# ProPrj_BS4C_00006_03_EasyEDA_2025-07-22.net
KiCad netlist of a schematic drawn in EasyEDA Pro
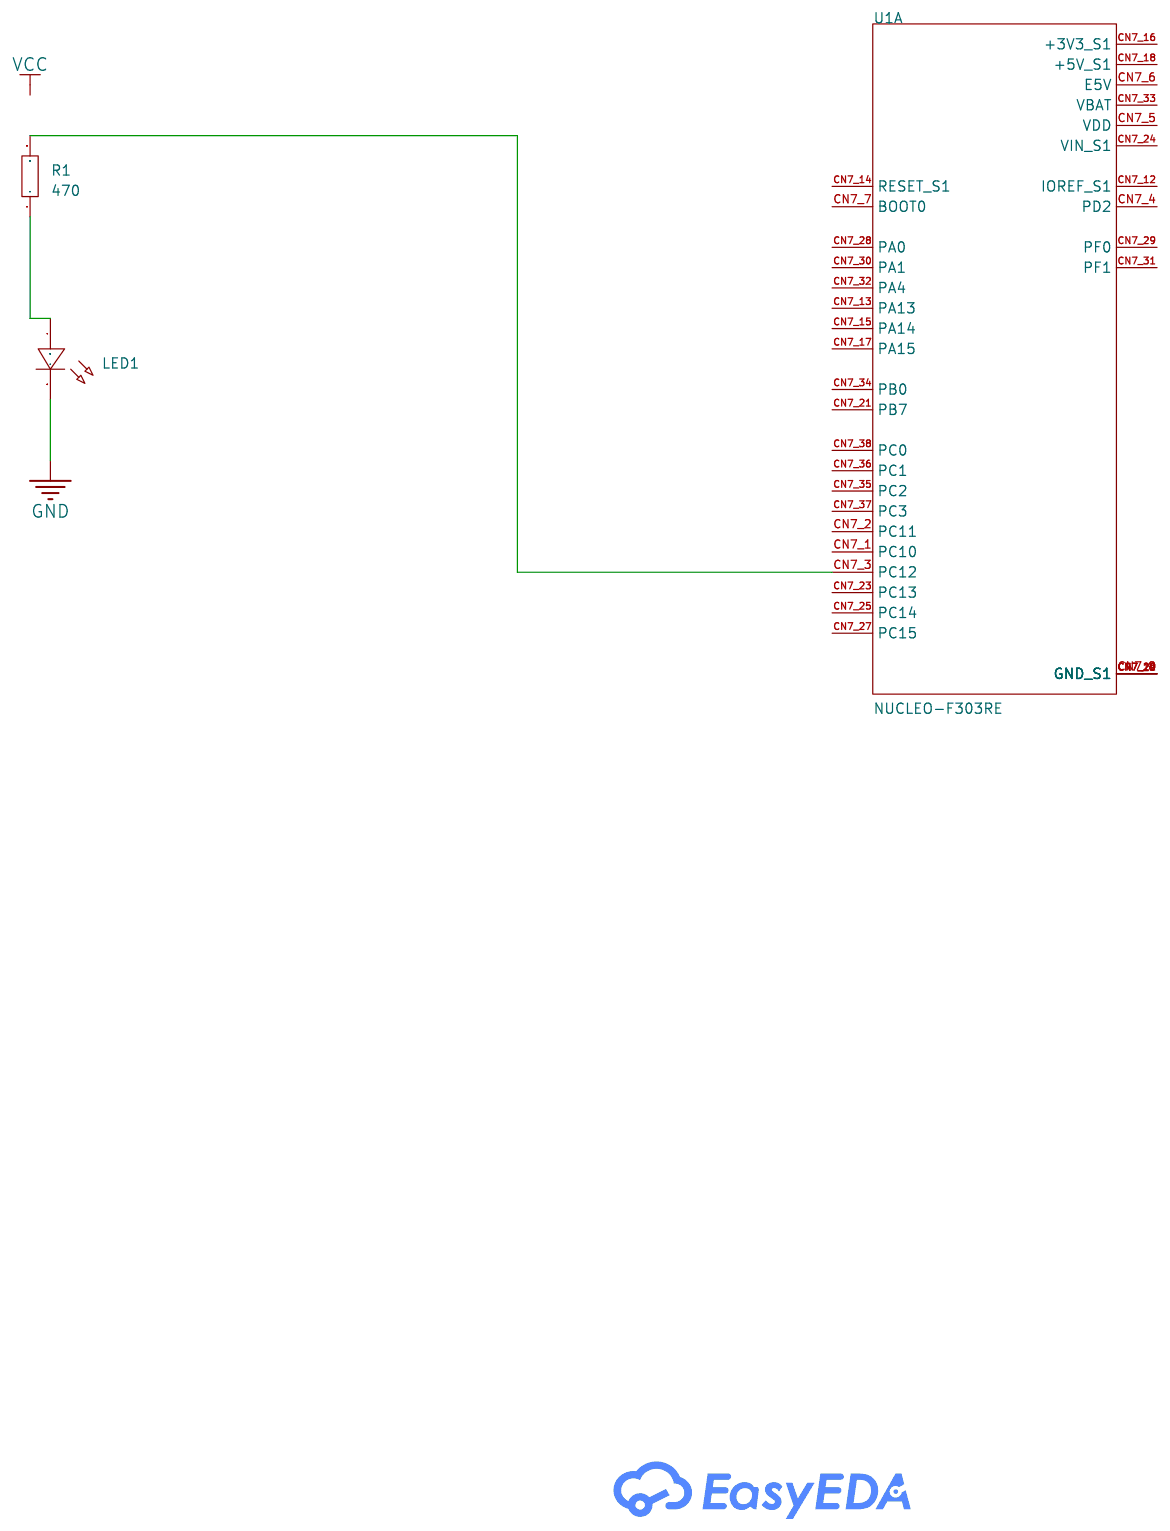
[diagram p0: schematic sheet]

(export (version "E")
  (design (tool "Eeschema 10.0.6"))
  (components
    (comp (ref "LED1")
      (value "~")
      (footprint "easyedapro:LED-TH_BD3.0-P2.54-FD")
      (libsource (lib "easyedapro") (part "LED_TH-R"))
    )
    (comp (ref "R1") (value "470") (footprint "easyedapro:R1210") (libsource (lib "easyedapro") (part "Res")))
    (comp (ref "U1") (value "NUCLEO-F303RE") (libsource (lib "easyedapro") (part "NUCLEO-F303RE")))
  )
  (nets
    (net (code "1") (name "GND") (class "Default")
      (node (ref "LED1") (pin "2") (pinfunction "A_2") (pintype "input"))
    )
    (net (code "2") (name "Net-(LED1-C)") (class "Default")
      (node (ref "LED1") (pin "1") (pinfunction "C_1") (pintype "input"))
      (node (ref "R1") (pin "1") (pinfunction "1_1") (pintype "input"))
    )
    (net (code "3") (name "Net-(U1A-GND_S1-PadCN7_19)") (class "Default")
      (node (ref "U1") (pin "CN7_19") (pinfunction "GND_S1_CN7_19") (pintype "unspecified"))
      (node (ref "U1") (pin "CN7_20") (pinfunction "GND_S1_CN7_20") (pintype "unspecified"))
      (node (ref "U1") (pin "CN7_22") (pinfunction "GND_S1_CN7_22") (pintype "unspecified"))
      (node (ref "U1") (pin "CN7_8") (pinfunction "GND_S1_CN7_8") (pintype "unspecified"))
    )
    (net (code "4") (name "Net-(U1A-PC12)") (class "Default")
      (node (ref "R1") (pin "2") (pinfunction "2_2") (pintype "input"))
      (node (ref "U1") (pin "CN7_3") (pinfunction "PC12_CN7_3") (pintype "bidirectional"))
    )
    (net (code "6") (name "unconnected-(U1A-+3V3_S1-PadCN7_16)") (class "Default")
      (node (ref "U1") (pin "CN7_16") (pinfunction "+3V3_S1_CN7_16") (pintype "unspecified"))
    )
    (net (code "7") (name "unconnected-(U1A-+5V_S1-PadCN7_18)") (class "Default")
      (node (ref "U1") (pin "CN7_18") (pinfunction "+5V_S1_CN7_18") (pintype "unspecified"))
    )
    (net (code "8") (name "unconnected-(U1A-BOOT0-PadCN7_7)") (class "Default")
      (node (ref "U1") (pin "CN7_7") (pinfunction "BOOT0_CN7_7") (pintype "bidirectional"))
    )
    (net (code "9") (name "unconnected-(U1A-E5V-PadCN7_6)") (class "Default")
      (node (ref "U1") (pin "CN7_6") (pinfunction "E5V_CN7_6") (pintype "unspecified"))
    )
    (net (code "10") (name "unconnected-(U1A-IOREF_S1-PadCN7_12)") (class "Default")
      (node (ref "U1") (pin "CN7_12") (pinfunction "IOREF_S1_CN7_12") (pintype "bidirectional"))
    )
    (net (code "11") (name "unconnected-(U1A-PA0-PadCN7_28)") (class "Default")
      (node (ref "U1") (pin "CN7_28") (pinfunction "PA0_CN7_28") (pintype "bidirectional"))
    )
    (net (code "12") (name "unconnected-(U1A-PA1-PadCN7_30)") (class "Default")
      (node (ref "U1") (pin "CN7_30") (pinfunction "PA1_CN7_30") (pintype "bidirectional"))
    )
    (net (code "13") (name "unconnected-(U1A-PA4-PadCN7_32)") (class "Default")
      (node (ref "U1") (pin "CN7_32") (pinfunction "PA4_CN7_32") (pintype "bidirectional"))
    )
    (net (code "14") (name "unconnected-(U1A-PA13-PadCN7_13)") (class "Default")
      (node (ref "U1") (pin "CN7_13") (pinfunction "PA13_CN7_13") (pintype "bidirectional"))
    )
    (net (code "15") (name "unconnected-(U1A-PA14-PadCN7_15)") (class "Default")
      (node (ref "U1") (pin "CN7_15") (pinfunction "PA14_CN7_15") (pintype "bidirectional"))
    )
    (net (code "16") (name "unconnected-(U1A-PA15-PadCN7_17)") (class "Default")
      (node (ref "U1") (pin "CN7_17") (pinfunction "PA15_CN7_17") (pintype "bidirectional"))
    )
    (net (code "17") (name "unconnected-(U1A-PB0-PadCN7_34)") (class "Default")
      (node (ref "U1") (pin "CN7_34") (pinfunction "PB0_CN7_34") (pintype "bidirectional"))
    )
    (net (code "18") (name "unconnected-(U1A-PB7-PadCN7_21)") (class "Default")
      (node (ref "U1") (pin "CN7_21") (pinfunction "PB7_CN7_21") (pintype "bidirectional"))
    )
    (net (code "19") (name "unconnected-(U1A-PC0-PadCN7_38)") (class "Default")
      (node (ref "U1") (pin "CN7_38") (pinfunction "PC0_CN7_38") (pintype "bidirectional"))
    )
    (net (code "20") (name "unconnected-(U1A-PC1-PadCN7_36)") (class "Default")
      (node (ref "U1") (pin "CN7_36") (pinfunction "PC1_CN7_36") (pintype "bidirectional"))
    )
    (net (code "21") (name "unconnected-(U1A-PC2-PadCN7_35)") (class "Default")
      (node (ref "U1") (pin "CN7_35") (pinfunction "PC2_CN7_35") (pintype "bidirectional"))
    )
    (net (code "22") (name "unconnected-(U1A-PC3-PadCN7_37)") (class "Default")
      (node (ref "U1") (pin "CN7_37") (pinfunction "PC3_CN7_37") (pintype "bidirectional"))
    )
    (net (code "23") (name "unconnected-(U1A-PC10-PadCN7_1)") (class "Default")
      (node (ref "U1") (pin "CN7_1") (pinfunction "PC10_CN7_1") (pintype "bidirectional"))
    )
    (net (code "24") (name "unconnected-(U1A-PC11-PadCN7_2)") (class "Default")
      (node (ref "U1") (pin "CN7_2") (pinfunction "PC11_CN7_2") (pintype "bidirectional"))
    )
    (net (code "25") (name "unconnected-(U1A-PC13-PadCN7_23)") (class "Default")
      (node (ref "U1") (pin "CN7_23") (pinfunction "PC13_CN7_23") (pintype "bidirectional"))
    )
    (net (code "26") (name "unconnected-(U1A-PC14-PadCN7_25)") (class "Default")
      (node (ref "U1") (pin "CN7_25") (pinfunction "PC14_CN7_25") (pintype "bidirectional"))
    )
    (net (code "27") (name "unconnected-(U1A-PC15-PadCN7_27)") (class "Default")
      (node (ref "U1") (pin "CN7_27") (pinfunction "PC15_CN7_27") (pintype "bidirectional"))
    )
    (net (code "28") (name "unconnected-(U1A-PD2-PadCN7_4)") (class "Default")
      (node (ref "U1") (pin "CN7_4") (pinfunction "PD2_CN7_4") (pintype "bidirectional"))
    )
    (net (code "29") (name "unconnected-(U1A-PF0-PadCN7_29)") (class "Default")
      (node (ref "U1") (pin "CN7_29") (pinfunction "PF0_CN7_29") (pintype "bidirectional"))
    )
    (net (code "30") (name "unconnected-(U1A-PF1-PadCN7_31)") (class "Default")
      (node (ref "U1") (pin "CN7_31") (pinfunction "PF1_CN7_31") (pintype "bidirectional"))
    )
    (net (code "31") (name "unconnected-(U1A-RESET_S1-PadCN7_14)") (class "Default")
      (node (ref "U1") (pin "CN7_14") (pinfunction "RESET_S1_CN7_14") (pintype "bidirectional"))
    )
    (net (code "32") (name "unconnected-(U1A-VBAT-PadCN7_33)") (class "Default")
      (node (ref "U1") (pin "CN7_33") (pinfunction "VBAT_CN7_33") (pintype "unspecified"))
    )
    (net (code "33") (name "unconnected-(U1A-VDD-PadCN7_5)") (class "Default")
      (node (ref "U1") (pin "CN7_5") (pinfunction "VDD_CN7_5") (pintype "unspecified"))
    )
    (net (code "34") (name "unconnected-(U1A-VIN_S1-PadCN7_24)") (class "Default")
      (node (ref "U1") (pin "CN7_24") (pinfunction "VIN_S1_CN7_24") (pintype "unspecified"))
    )
  )
)
